# 05-USB-Prog.net
KiCad netlist of a schematic drawn in Altium Designer
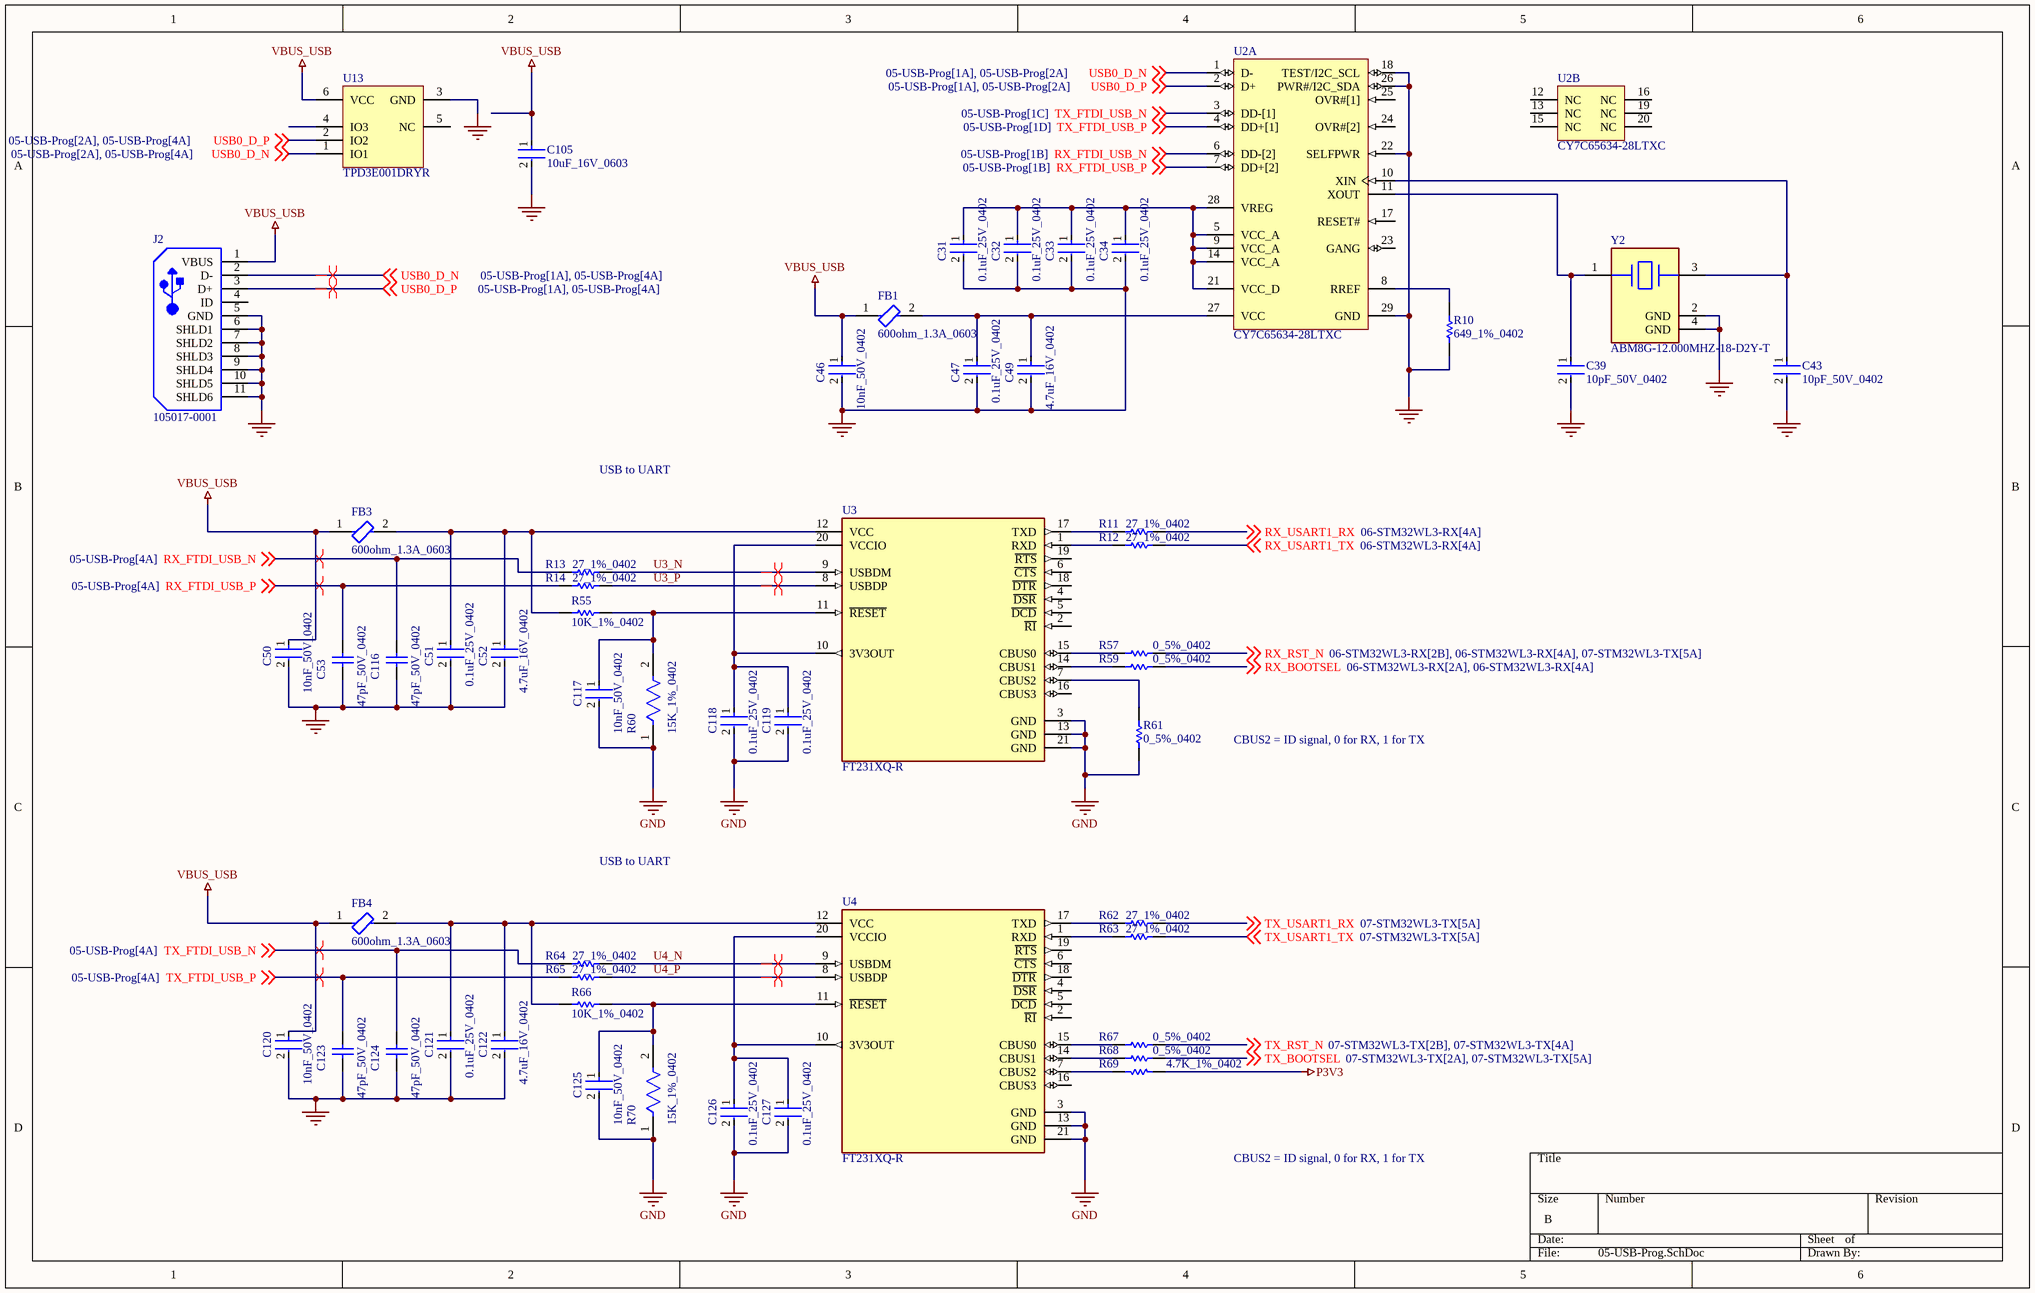
[diagram p0: 05-USB-Prog.SchDoc]

(export (version "E")
  (design (tool "Eeschema 10.0.6"))
  (components
    (comp (ref "C31")
      (value "0.1uF_25V_0402")
      (footprint "FP-0402-L_1_0_1-W_0_5_0_1-IPC_C")
      (description "General Purpose Ceramic Capacitor, 0402, 100nF, 10%, X7R, 15%, 25V")
      (fields (field (name "VOLTAGE") "25V") (field (name "TOLERANCE") "10%"))
      (libsource (lib "Altium Content Vault") (part "b4654b650e69147ec39a6b967a45e02"))
    )
    (comp (ref "C32")
      (value "0.1uF_25V_0402")
      (footprint "FP-0402-L_1_0_1-W_0_5_0_1-IPC_C")
      (description "General Purpose Ceramic Capacitor, 0402, 100nF, 10%, X7R, 15%, 25V")
      (fields (field (name "VOLTAGE") "25V") (field (name "TOLERANCE") "10%"))
      (libsource (lib "Altium Content Vault") (part "b4654b650e69147ec39a6b967a45e02"))
    )
    (comp (ref "C33")
      (value "0.1uF_25V_0402")
      (footprint "FP-0402-L_1_0_1-W_0_5_0_1-IPC_C")
      (description "General Purpose Ceramic Capacitor, 0402, 100nF, 10%, X7R, 15%, 25V")
      (fields (field (name "VOLTAGE") "25V") (field (name "TOLERANCE") "10%"))
      (libsource (lib "Altium Content Vault") (part "b4654b650e69147ec39a6b967a45e02"))
    )
    (comp (ref "C34")
      (value "0.1uF_25V_0402")
      (footprint "FP-0402-L_1_0_1-W_0_5_0_1-IPC_C")
      (description "General Purpose Ceramic Capacitor, 0402, 100nF, 10%, X7R, 15%, 25V")
      (fields (field (name "VOLTAGE") "25V") (field (name "TOLERANCE") "10%"))
      (libsource (lib "Altium Content Vault") (part "b4654b650e69147ec39a6b967a45e02"))
    )
    (comp (ref "C39")
      (value "10pF_50V_0402")
      (footprint "FP-C1005-050-0_05-IPC_C")
      (description "CAP CER 10PF 50V C0G 0402")
      (fields (field (name "VOLTAGE") "50V"))
      (libsource (lib "Altium Content Vault") (part "b4654b650e69147ec39a6b967a45e02"))
    )
    (comp (ref "C43")
      (value "10pF_50V_0402")
      (footprint "FP-C1005-050-0_05-IPC_C")
      (description "CAP CER 10PF 50V C0G 0402")
      (fields (field (name "VOLTAGE") "50V"))
      (libsource (lib "Altium Content Vault") (part "b4654b650e69147ec39a6b967a45e02"))
    )
    (comp (ref "C46")
      (value "10nF_50V_0402")
      (footprint "FP-CC0402-MFG")
      (description "CAP CER 10000PF 50V X7R 0402")
      (fields
        (field (name "OCTOPART") "https://octopart.com/cc0402krx7r9bb103-yageo-8376513")
        (field (name "MANUFACTURER PART NUMBER") "CC0402KRX7R9BB103")
      )
      (libsource (lib "Altium Content Vault") (part "11868f565c42a9108669ba33697ecf6"))
    )
    (comp (ref "C47")
      (value "0.1uF_25V_0402")
      (footprint "FP-0402-L_1_0_1-W_0_5_0_1-IPC_C")
      (description "General Purpose Ceramic Capacitor, 0402, 100nF, 10%, X7R, 15%, 25V")
      (fields (field (name "VOLTAGE") "25V") (field (name "TOLERANCE") "10%"))
      (libsource (lib "Altium Content Vault") (part "b4654b650e69147ec39a6b967a45e02"))
    )
    (comp (ref "C49")
      (value "4.7uF_16V_0402")
      (footprint "FP-CL829-IPC_C")
      (description "Cap Ceramic 4.7uF 16V X5R ±20% SMD 0402 +85°C Paper T/R")
      (fields (field (name "TOLERANCE") "20%"))
      (libsource (lib "Altium Content Vault") (part "b4654b650e69147ec39a6b967a45e02"))
    )
    (comp (ref "C50")
      (value "10nF_50V_0402")
      (footprint "FP-CC0402-MFG")
      (description "CAP CER 10000PF 50V X7R 0402")
      (fields
        (field (name "OCTOPART") "https://octopart.com/cc0402krx7r9bb103-yageo-8376513")
        (field (name "MANUFACTURER PART NUMBER") "CC0402KRX7R9BB103")
      )
      (libsource (lib "Altium Content Vault") (part "11868f565c42a9108669ba33697ecf6"))
    )
    (comp (ref "C51")
      (value "0.1uF_25V_0402")
      (footprint "FP-0402-L_1_0_1-W_0_5_0_1-IPC_C")
      (description "General Purpose Ceramic Capacitor, 0402, 100nF, 10%, X7R, 15%, 25V")
      (fields (field (name "VOLTAGE") "25V") (field (name "TOLERANCE") "10%"))
      (libsource (lib "Altium Content Vault") (part "b4654b650e69147ec39a6b967a45e02"))
    )
    (comp (ref "C52")
      (value "4.7uF_16V_0402")
      (footprint "FP-CL829-IPC_C")
      (description "Cap Ceramic 4.7uF 16V X5R ±20% SMD 0402 +85°C Paper T/R")
      (fields (field (name "TOLERANCE") "20%"))
      (libsource (lib "Altium Content Vault") (part "b4654b650e69147ec39a6b967a45e02"))
    )
    (comp (ref "C53")
      (value "47pF_50V_0402")
      (footprint "CAPC1005X55X25LL05T10")
      (fields (field (name "PART NUMBER") "GRM1555C1H470JA01D") (field (name "MANUFACTURER") "Murata"))
      (libsource (lib "Altium Content Vault") (part "CAP"))
    )
    (comp (ref "C105")
      (value "10uF_16V_0603")
      (footprint "FP-0603-L_1_6_0_2-W_0_8_0-MFG")
      (description "Multilayer Ceramic Capacitor 10uF 16V X5R 20% SMD 0603 T/R")
      (fields (field (name "TOLERANCE") "20%"))
      (libsource (lib "Altium Content Vault") (part "b4654b650e69147ec39a6b967a45e02"))
    )
    (comp (ref "C116")
      (value "47pF_50V_0402")
      (footprint "CAPC1005X55X25LL05T10")
      (fields (field (name "PART NUMBER") "GRM1555C1H470JA01D") (field (name "MANUFACTURER") "Murata"))
      (libsource (lib "Altium Content Vault") (part "CAP"))
    )
    (comp (ref "C117")
      (value "10nF_50V_0402")
      (footprint "FP-CC0402-MFG")
      (description "CAP CER 10000PF 50V X7R 0402")
      (fields
        (field (name "OCTOPART") "https://octopart.com/cc0402krx7r9bb103-yageo-8376513")
        (field (name "MANUFACTURER PART NUMBER") "CC0402KRX7R9BB103")
      )
      (libsource (lib "Altium Content Vault") (part "11868f565c42a9108669ba33697ecf6"))
    )
    (comp (ref "C118")
      (value "0.1uF_25V_0402")
      (footprint "FP-0402-L_1_0_1-W_0_5_0_1-IPC_C")
      (description "General Purpose Ceramic Capacitor, 0402, 100nF, 10%, X7R, 15%, 25V")
      (fields (field (name "VOLTAGE") "25V") (field (name "TOLERANCE") "10%"))
      (libsource (lib "Altium Content Vault") (part "b4654b650e69147ec39a6b967a45e02"))
    )
    (comp (ref "C119")
      (value "0.1uF_25V_0402")
      (footprint "FP-0402-L_1_0_1-W_0_5_0_1-IPC_C")
      (description "General Purpose Ceramic Capacitor, 0402, 100nF, 10%, X7R, 15%, 25V")
      (fields (field (name "VOLTAGE") "25V") (field (name "TOLERANCE") "10%"))
      (libsource (lib "Altium Content Vault") (part "b4654b650e69147ec39a6b967a45e02"))
    )
    (comp (ref "C120")
      (value "10nF_50V_0402")
      (footprint "FP-CC0402-MFG")
      (description "CAP CER 10000PF 50V X7R 0402")
      (fields
        (field (name "OCTOPART") "https://octopart.com/cc0402krx7r9bb103-yageo-8376513")
        (field (name "MANUFACTURER PART NUMBER") "CC0402KRX7R9BB103")
      )
      (libsource (lib "Altium Content Vault") (part "11868f565c42a9108669ba33697ecf6"))
    )
    (comp (ref "C121")
      (value "0.1uF_25V_0402")
      (footprint "FP-0402-L_1_0_1-W_0_5_0_1-IPC_C")
      (description "General Purpose Ceramic Capacitor, 0402, 100nF, 10%, X7R, 15%, 25V")
      (fields (field (name "VOLTAGE") "25V") (field (name "TOLERANCE") "10%"))
      (libsource (lib "Altium Content Vault") (part "b4654b650e69147ec39a6b967a45e02"))
    )
    (comp (ref "C122")
      (value "4.7uF_16V_0402")
      (footprint "FP-CL829-IPC_C")
      (description "Cap Ceramic 4.7uF 16V X5R ±20% SMD 0402 +85°C Paper T/R")
      (fields (field (name "TOLERANCE") "20%"))
      (libsource (lib "Altium Content Vault") (part "b4654b650e69147ec39a6b967a45e02"))
    )
    (comp (ref "C123")
      (value "47pF_50V_0402")
      (footprint "CAPC1005X55X25LL05T10")
      (fields (field (name "PART NUMBER") "GRM1555C1H470JA01D") (field (name "MANUFACTURER") "Murata"))
      (libsource (lib "Altium Content Vault") (part "CAP"))
    )
    (comp (ref "C124")
      (value "47pF_50V_0402")
      (footprint "CAPC1005X55X25LL05T10")
      (fields (field (name "PART NUMBER") "GRM1555C1H470JA01D") (field (name "MANUFACTURER") "Murata"))
      (libsource (lib "Altium Content Vault") (part "CAP"))
    )
    (comp (ref "C125")
      (value "10nF_50V_0402")
      (footprint "FP-CC0402-MFG")
      (description "CAP CER 10000PF 50V X7R 0402")
      (fields
        (field (name "OCTOPART") "https://octopart.com/cc0402krx7r9bb103-yageo-8376513")
        (field (name "MANUFACTURER PART NUMBER") "CC0402KRX7R9BB103")
      )
      (libsource (lib "Altium Content Vault") (part "11868f565c42a9108669ba33697ecf6"))
    )
    (comp (ref "C126")
      (value "0.1uF_25V_0402")
      (footprint "FP-0402-L_1_0_1-W_0_5_0_1-IPC_C")
      (description "General Purpose Ceramic Capacitor, 0402, 100nF, 10%, X7R, 15%, 25V")
      (fields (field (name "VOLTAGE") "25V") (field (name "TOLERANCE") "10%"))
      (libsource (lib "Altium Content Vault") (part "b4654b650e69147ec39a6b967a45e02"))
    )
    (comp (ref "C127")
      (value "0.1uF_25V_0402")
      (footprint "FP-0402-L_1_0_1-W_0_5_0_1-IPC_C")
      (description "General Purpose Ceramic Capacitor, 0402, 100nF, 10%, X7R, 15%, 25V")
      (fields (field (name "VOLTAGE") "25V") (field (name "TOLERANCE") "10%"))
      (libsource (lib "Altium Content Vault") (part "b4654b650e69147ec39a6b967a45e02"))
    )
    (comp (ref "FB1")
      (value "600ohm_1.3A_0603")
      (footprint "FP-BLM18-0_15-t0_8-IPC_A")
      (description "Chip Ferrite Bead, 0603, 600Ω @ 100MHz, 0.15Ω, 25%, 1.3A")
      (fields (field (name "TOLERANCE") "25%"))
      (libsource (lib "Altium Content Vault") (part "5f30dd21d616792df468990f7003faa"))
    )
    (comp (ref "FB3")
      (value "600ohm_1.3A_0603")
      (footprint "FP-BLM18-0_15-t0_8-IPC_A")
      (description "Chip Ferrite Bead, 0603, 600Ω @ 100MHz, 0.15Ω, 25%, 1.3A")
      (fields (field (name "TOLERANCE") "25%"))
      (libsource (lib "Altium Content Vault") (part "5f30dd21d616792df468990f7003faa"))
    )
    (comp (ref "FB4")
      (value "600ohm_1.3A_0603")
      (footprint "FP-BLM18-0_15-t0_8-IPC_A")
      (description "Chip Ferrite Bead, 0603, 600Ω @ 100MHz, 0.15Ω, 25%, 1.3A")
      (fields (field (name "TOLERANCE") "25%"))
      (libsource (lib "Altium Content Vault") (part "5f30dd21d616792df468990f7003faa"))
    )
    (comp (ref "J2")
      (value "105017-0001")
      (footprint "USB-MICRO-B_V")
      (fields (field (name "MANUFACTURER") "Molex"))
      (libsource (lib "Altium Content Vault") (part "USB-5-6SHLD"))
    )
    (comp (ref "R10")
      (value "649_1%_0402")
      (footprint "RESC1005X40X25LL05T05")
      (fields (field (name "PART NUMBER") "ERJ-2RKF6490X") (field (name "MANUFACTURER") "Panasonic"))
      (libsource (lib "Altium Content Vault") (part "RES"))
    )
    (comp (ref "R11")
      (value "27_1%_0402")
      (footprint "RESC1005X40X25NL05T05")
      (fields (field (name "PART NUMBER") "CRCW040227R0FKED") (field (name "MANUFACTURER") "Vishay Dale"))
      (libsource (lib "Altium Content Vault") (part "RES"))
    )
    (comp (ref "R12")
      (value "27_1%_0402")
      (footprint "RESC1005X40X25NL05T05")
      (fields (field (name "PART NUMBER") "CRCW040227R0FKED") (field (name "MANUFACTURER") "Vishay Dale"))
      (libsource (lib "Altium Content Vault") (part "RES"))
    )
    (comp (ref "R13")
      (value "27_1%_0402")
      (footprint "RESC1005X40X25NL05T05")
      (fields (field (name "PART NUMBER") "CRCW040227R0FKED") (field (name "MANUFACTURER") "Vishay Dale"))
      (libsource (lib "Altium Content Vault") (part "RES"))
    )
    (comp (ref "R14")
      (value "27_1%_0402")
      (footprint "RESC1005X40X25NL05T05")
      (fields (field (name "PART NUMBER") "CRCW040227R0FKED") (field (name "MANUFACTURER") "Vishay Dale"))
      (libsource (lib "Altium Content Vault") (part "RES"))
    )
    (comp (ref "R55")
      (value "10K_1%_0402")
      (footprint "RESC1005X40X25LL05T10")
      (fields (field (name "PART NUMBER") "RC0402FR-0710KL") (field (name "MANUFACTURER") "Yageo / Phycomp"))
      (libsource (lib "Altium Content Vault") (part "RES"))
    )
    (comp (ref "R57")
      (value "0_5%_0402")
      (footprint "RESC1005X40X25NL05T10")
      (fields (field (name "MANUFACTURER") "Panasonic") (field (name "PART NUMBER") "ERJ-U020R00X"))
      (libsource (lib "Altium Content Vault") (part "RES"))
    )
    (comp (ref "R59")
      (value "0_5%_0402")
      (footprint "RESC1005X40X25NL05T10")
      (fields (field (name "MANUFACTURER") "Panasonic") (field (name "PART NUMBER") "ERJ-U020R00X"))
      (libsource (lib "Altium Content Vault") (part "RES"))
    )
    (comp (ref "R60")
      (value "15K_1%_0402")
      (footprint "FP-ERJ2R-MFG")
      (description "RES SMD 15K OHM 1% 1/10W 0402")
      (fields (field (name "TOLERANCE") "1%") (field (name "MANUFACTURER PART NUMBER") "ERJ-2RKF1502X"))
      (libsource (lib "Altium Content Vault") (part "1029c3af85768c4190bb7ad29bc67b5"))
    )
    (comp (ref "R61")
      (value "0_5%_0402")
      (footprint "RESC1005X40X25NL05T10")
      (fields (field (name "MANUFACTURER") "Panasonic") (field (name "PART NUMBER") "ERJ-U020R00X"))
      (libsource (lib "Altium Content Vault") (part "RES"))
    )
    (comp (ref "R62")
      (value "27_1%_0402")
      (footprint "RESC1005X40X25NL05T05")
      (fields (field (name "PART NUMBER") "CRCW040227R0FKED") (field (name "MANUFACTURER") "Vishay Dale"))
      (libsource (lib "Altium Content Vault") (part "RES"))
    )
    (comp (ref "R63")
      (value "27_1%_0402")
      (footprint "RESC1005X40X25NL05T05")
      (fields (field (name "PART NUMBER") "CRCW040227R0FKED") (field (name "MANUFACTURER") "Vishay Dale"))
      (libsource (lib "Altium Content Vault") (part "RES"))
    )
    (comp (ref "R64")
      (value "27_1%_0402")
      (footprint "RESC1005X40X25NL05T05")
      (fields (field (name "PART NUMBER") "CRCW040227R0FKED") (field (name "MANUFACTURER") "Vishay Dale"))
      (libsource (lib "Altium Content Vault") (part "RES"))
    )
    (comp (ref "R65")
      (value "27_1%_0402")
      (footprint "RESC1005X40X25NL05T05")
      (fields (field (name "PART NUMBER") "CRCW040227R0FKED") (field (name "MANUFACTURER") "Vishay Dale"))
      (libsource (lib "Altium Content Vault") (part "RES"))
    )
    (comp (ref "R66")
      (value "10K_1%_0402")
      (footprint "RESC1005X40X25LL05T10")
      (fields (field (name "PART NUMBER") "RC0402FR-0710KL") (field (name "MANUFACTURER") "Yageo / Phycomp"))
      (libsource (lib "Altium Content Vault") (part "RES"))
    )
    (comp (ref "R67")
      (value "0_5%_0402")
      (footprint "RESC1005X40X25NL05T10")
      (fields (field (name "MANUFACTURER") "Panasonic") (field (name "PART NUMBER") "ERJ-U020R00X"))
      (libsource (lib "Altium Content Vault") (part "RES"))
    )
    (comp (ref "R68")
      (value "0_5%_0402")
      (footprint "RESC1005X40X25NL05T10")
      (fields (field (name "MANUFACTURER") "Panasonic") (field (name "PART NUMBER") "ERJ-U020R00X"))
      (libsource (lib "Altium Content Vault") (part "RES"))
    )
    (comp (ref "R69")
      (value "4.7K_1%_0402")
      (footprint "RESC1005X40X25NL10T10")
      (fields (field (name "MANUFACTURER") "Bourns") (field (name "PART NUMBER") "CR0402-FX-4701GLF"))
      (libsource (lib "Altium Content Vault") (part "RES"))
    )
    (comp (ref "R70")
      (value "15K_1%_0402")
      (footprint "FP-ERJ2R-MFG")
      (description "RES SMD 15K OHM 1% 1/10W 0402")
      (fields (field (name "TOLERANCE") "1%") (field (name "MANUFACTURER PART NUMBER") "ERJ-2RKF1502X"))
      (libsource (lib "Altium Content Vault") (part "1029c3af85768c4190bb7ad29bc67b5"))
    )
    (comp (ref "U2")
      (value "CY7C65634-28LTXC")
      (footprint "CYP-LTX28_M")
      (fields (field (name "MANUFACTURER") "Cypress"))
      (libsource (lib "Altium Content Vault") (part "CYP-CY7C65634-LT28"))
    )
    (comp (ref "U3")
      (value "FT231XQ-R")
      (footprint "FP-QFN-20-MFG")
      (description "IC USB SERIAL FULL UART 20QFN")
      (libsource (lib "Altium Content Vault") (part "1a58eaec777a01ae16a7011961d8d4e"))
    )
    (comp (ref "U4")
      (value "FT231XQ-R")
      (footprint "FP-QFN-20-MFG")
      (description "IC USB SERIAL FULL UART 20QFN")
      (libsource (lib "Altium Content Vault") (part "1a58eaec777a01ae16a7011961d8d4e"))
    )
    (comp (ref "U13")
      (value "TPD3E001DRYR")
      (footprint "DRY0006A")
      (fields (field (name "MANUFACTURER") "Texas Instruments"))
      (libsource (lib "Altium Content Vault") (part "TI-TPD3E001-SON_DRY-6"))
    )
    (comp (ref "Y2")
      (value "ABM8G-12.000MHZ-18-D2Y-T")
      (footprint "FP-ABM8G-MFG")
      (description "Crystal 12MHz ±20ppm (Tol) ±30ppm (Stability) 18pF FUND 120Ω 4-Pin SMD T/R")
      (fields (field (name "TOLERANCE") "20ppm"))
      (libsource (lib "Altium Content Vault") (part "48e526d86b7f2615d98721063c72f49"))
    )
  )
  (nets
    (net (code "1") (name "/U3_N") (class "Default")
      (node (ref "R13") (pin "2") (pinfunction "2_2") (pintype "passive"))
      (node (ref "U3") (pin "9") (pinfunction "USBDM_9") (pintype "input"))
    )
    (net (code "2") (name "/U3_P") (class "Default")
      (node (ref "R14") (pin "2") (pinfunction "2_2") (pintype "passive"))
      (node (ref "U3") (pin "8") (pinfunction "USBDP_8") (pintype "input"))
    )
    (net (code "3") (name "/U4_N") (class "Default")
      (node (ref "R64") (pin "2") (pinfunction "2_2") (pintype "passive"))
      (node (ref "U4") (pin "9") (pinfunction "USBDM_9") (pintype "input"))
    )
    (net (code "4") (name "/U4_P") (class "Default")
      (node (ref "R65") (pin "2") (pinfunction "2_2") (pintype "passive"))
      (node (ref "U4") (pin "8") (pinfunction "USBDP_8") (pintype "input"))
    )
    (net (code "5") (name "GND") (class "Default")
      (node (ref "C105") (pin "2") (pinfunction "2_2") (pintype "passive"))
      (node (ref "C116") (pin "1") (pinfunction "1_1") (pintype "passive"))
      (node (ref "C117") (pin "2") (pinfunction "2_2") (pintype "passive"))
      (node (ref "C118") (pin "2") (pinfunction "2_2") (pintype "passive"))
      (node (ref "C119") (pin "2") (pinfunction "2_2") (pintype "passive"))
      (node (ref "C120") (pin "2") (pinfunction "2_2") (pintype "passive"))
      (node (ref "C121") (pin "2") (pinfunction "2_2") (pintype "passive"))
      (node (ref "C122") (pin "2") (pinfunction "2_2") (pintype "passive"))
      (node (ref "C123") (pin "1") (pinfunction "1_1") (pintype "passive"))
      (node (ref "C124") (pin "1") (pinfunction "1_1") (pintype "passive"))
      (node (ref "C125") (pin "2") (pinfunction "2_2") (pintype "passive"))
      (node (ref "C126") (pin "2") (pinfunction "2_2") (pintype "passive"))
      (node (ref "C127") (pin "2") (pinfunction "2_2") (pintype "passive"))
      (node (ref "C31") (pin "2") (pinfunction "2_2") (pintype "passive"))
      (node (ref "C32") (pin "2") (pinfunction "2_2") (pintype "passive"))
      (node (ref "C33") (pin "2") (pinfunction "2_2") (pintype "passive"))
      (node (ref "C34") (pin "2") (pinfunction "2_2") (pintype "passive"))
      (node (ref "C39") (pin "2") (pinfunction "2_2") (pintype "passive"))
      (node (ref "C43") (pin "2") (pinfunction "2_2") (pintype "passive"))
      (node (ref "C46") (pin "2") (pinfunction "2_2") (pintype "passive"))
      (node (ref "C47") (pin "2") (pinfunction "2_2") (pintype "passive"))
      (node (ref "C49") (pin "2") (pinfunction "2_2") (pintype "passive"))
      (node (ref "C50") (pin "2") (pinfunction "2_2") (pintype "passive"))
      (node (ref "C51") (pin "2") (pinfunction "2_2") (pintype "passive"))
      (node (ref "C52") (pin "2") (pinfunction "2_2") (pintype "passive"))
      (node (ref "C53") (pin "1") (pinfunction "1_1") (pintype "passive"))
      (node (ref "J2") (pin "10") (pinfunction "SHLD5_10") (pintype "passive"))
      (node (ref "J2") (pin "11") (pinfunction "SHLD6_11") (pintype "passive"))
      (node (ref "J2") (pin "5") (pinfunction "GND_5") (pintype "passive"))
      (node (ref "J2") (pin "6") (pinfunction "SHLD1_6") (pintype "passive"))
      (node (ref "J2") (pin "7") (pinfunction "SHLD2_7") (pintype "passive"))
      (node (ref "J2") (pin "8") (pinfunction "SHLD3_8") (pintype "passive"))
      (node (ref "J2") (pin "9") (pinfunction "SHLD4_9") (pintype "passive"))
      (node (ref "R10") (pin "1") (pinfunction "1_1") (pintype "passive"))
      (node (ref "R60") (pin "1") (pinfunction "1_1") (pintype "passive"))
      (node (ref "R61") (pin "1") (pinfunction "1_1") (pintype "passive"))
      (node (ref "R70") (pin "1") (pinfunction "1_1") (pintype "passive"))
      (node (ref "U13") (pin "3") (pinfunction "GND_3") (pintype "power_in"))
      (node (ref "U2") (pin "18") (pinfunction "TEST/I2C_SCL_18") (pintype "bidirectional"))
      (node (ref "U2") (pin "22") (pinfunction "SELFPWR_22") (pintype "input"))
      (node (ref "U2") (pin "26") (pinfunction "PWR#/I2C_SDA_26") (pintype "bidirectional"))
      (node (ref "U2") (pin "29") (pinfunction "GND_29") (pintype "power_in"))
      (node (ref "U3") (pin "13") (pinfunction "GND_13") (pintype "open_emitter"))
      (node (ref "U3") (pin "21") (pinfunction "GND_21") (pintype "power_in"))
      (node (ref "U3") (pin "3") (pinfunction "GND_3") (pintype "power_in"))
      (node (ref "U4") (pin "13") (pinfunction "GND_13") (pintype "open_emitter"))
      (node (ref "U4") (pin "21") (pinfunction "GND_21") (pintype "power_in"))
      (node (ref "U4") (pin "3") (pinfunction "GND_3") (pintype "power_in"))
      (node (ref "Y2") (pin "2") (pinfunction "GND_2") (pintype "power_in"))
      (node (ref "Y2") (pin "4") (pinfunction "GND_4") (pintype "power_in"))
    )
    (net (code "6") (name "Net-(U2A-RREF)") (class "Default")
      (node (ref "R10") (pin "2") (pinfunction "2_2") (pintype "passive"))
      (node (ref "U2") (pin "8") (pinfunction "RREF_8") (pintype "passive"))
    )
    (net (code "7") (name "Net-(U2A-VCC)") (class "Default")
      (node (ref "C47") (pin "1") (pinfunction "1_1") (pintype "passive"))
      (node (ref "C49") (pin "1") (pinfunction "1_1") (pintype "passive"))
      (node (ref "FB1") (pin "2") (pinfunction "2_2") (pintype "passive"))
      (node (ref "U2") (pin "27") (pinfunction "VCC_27") (pintype "power_in"))
    )
    (net (code "8") (name "Net-(U2A-VCC_D)") (class "Default")
      (node (ref "C31") (pin "1") (pinfunction "1_1") (pintype "passive"))
      (node (ref "C32") (pin "1") (pinfunction "1_1") (pintype "passive"))
      (node (ref "C33") (pin "1") (pinfunction "1_1") (pintype "passive"))
      (node (ref "C34") (pin "1") (pinfunction "1_1") (pintype "passive"))
      (node (ref "U2") (pin "14") (pinfunction "VCC_A_14") (pintype "power_in"))
      (node (ref "U2") (pin "21") (pinfunction "VCC_D_21") (pintype "power_in"))
      (node (ref "U2") (pin "28") (pinfunction "VREG_28") (pintype "power_in"))
      (node (ref "U2") (pin "5") (pinfunction "VCC_A_5") (pintype "power_in"))
      (node (ref "U2") (pin "9") (pinfunction "VCC_A_9") (pintype "power_in"))
    )
    (net (code "9") (name "Net-(U2A-XIN)") (class "Default")
      (node (ref "C43") (pin "1") (pinfunction "1_1") (pintype "passive"))
      (node (ref "U2") (pin "10") (pinfunction "XIN_10") (pintype "input"))
      (node (ref "Y2") (pin "3") (pinfunction "3_3") (pintype "passive"))
    )
    (net (code "10") (name "Net-(U2A-XOUT)") (class "Default")
      (node (ref "C39") (pin "1") (pinfunction "1_1") (pintype "passive"))
      (node (ref "U2") (pin "11") (pinfunction "XOUT_11") (pintype "passive"))
      (node (ref "Y2") (pin "1") (pinfunction "1_1") (pintype "passive"))
    )
    (net (code "11") (name "Net-(U3-3V3OUT)") (class "Default")
      (node (ref "C118") (pin "1") (pinfunction "1_1") (pintype "passive"))
      (node (ref "C119") (pin "1") (pinfunction "1_1") (pintype "passive"))
      (node (ref "U3") (pin "10") (pinfunction "3V3OUT_10") (pintype "output"))
      (node (ref "U3") (pin "20") (pinfunction "VCCIO_20") (pintype "power_in"))
    )
    (net (code "12") (name "Net-(U3-CBUS0)") (class "Default")
      (node (ref "R57") (pin "1") (pinfunction "1_1") (pintype "passive"))
      (node (ref "U3") (pin "15") (pinfunction "CBUS0_15") (pintype "bidirectional"))
    )
    (net (code "13") (name "Net-(U3-CBUS1)") (class "Default")
      (node (ref "R59") (pin "1") (pinfunction "1_1") (pintype "passive"))
      (node (ref "U3") (pin "14") (pinfunction "CBUS1_14") (pintype "bidirectional"))
    )
    (net (code "14") (name "Net-(U3-CBUS2)") (class "Default")
      (node (ref "R61") (pin "2") (pinfunction "2_2") (pintype "passive"))
      (node (ref "U3") (pin "7") (pinfunction "CBUS2_7") (pintype "bidirectional"))
    )
    (net (code "15") (name "Net-(U3-RXD)") (class "Default")
      (node (ref "R12") (pin "1") (pinfunction "1_1") (pintype "passive"))
      (node (ref "U3") (pin "1") (pinfunction "RXD_1") (pintype "input"))
    )
    (net (code "16") (name "Net-(U3-TXD)") (class "Default")
      (node (ref "R11") (pin "1") (pinfunction "1_1") (pintype "passive"))
      (node (ref "U3") (pin "17") (pinfunction "TXD_17") (pintype "output"))
    )
    (net (code "17") (name "Net-(U3-VCC)") (class "Default")
      (node (ref "C51") (pin "1") (pinfunction "1_1") (pintype "passive"))
      (node (ref "C52") (pin "1") (pinfunction "1_1") (pintype "passive"))
      (node (ref "FB3") (pin "2") (pinfunction "2_2") (pintype "passive"))
      (node (ref "R55") (pin "2") (pinfunction "2_2") (pintype "passive"))
      (node (ref "U3") (pin "12") (pinfunction "VCC_12") (pintype "power_in"))
    )
    (net (code "18") (name "Net-(U3-~{RESET})") (class "Default")
      (node (ref "C117") (pin "1") (pinfunction "1_1") (pintype "passive"))
      (node (ref "R55") (pin "1") (pinfunction "1_1") (pintype "passive"))
      (node (ref "R60") (pin "2") (pinfunction "2_2") (pintype "passive"))
      (node (ref "U3") (pin "11") (pinfunction "~{RESET}_11") (pintype "input"))
    )
    (net (code "19") (name "Net-(U4-3V3OUT)") (class "Default")
      (node (ref "C126") (pin "1") (pinfunction "1_1") (pintype "passive"))
      (node (ref "C127") (pin "1") (pinfunction "1_1") (pintype "passive"))
      (node (ref "U4") (pin "10") (pinfunction "3V3OUT_10") (pintype "output"))
      (node (ref "U4") (pin "20") (pinfunction "VCCIO_20") (pintype "power_in"))
    )
    (net (code "20") (name "Net-(U4-CBUS0)") (class "Default")
      (node (ref "R67") (pin "1") (pinfunction "1_1") (pintype "passive"))
      (node (ref "U4") (pin "15") (pinfunction "CBUS0_15") (pintype "bidirectional"))
    )
    (net (code "21") (name "Net-(U4-CBUS1)") (class "Default")
      (node (ref "R68") (pin "1") (pinfunction "1_1") (pintype "passive"))
      (node (ref "U4") (pin "14") (pinfunction "CBUS1_14") (pintype "bidirectional"))
    )
    (net (code "22") (name "Net-(U4-CBUS2)") (class "Default")
      (node (ref "R69") (pin "2") (pinfunction "2_2") (pintype "passive"))
      (node (ref "U4") (pin "7") (pinfunction "CBUS2_7") (pintype "bidirectional"))
    )
    (net (code "23") (name "Net-(U4-RXD)") (class "Default")
      (node (ref "R63") (pin "1") (pinfunction "1_1") (pintype "passive"))
      (node (ref "U4") (pin "1") (pinfunction "RXD_1") (pintype "input"))
    )
    (net (code "24") (name "Net-(U4-TXD)") (class "Default")
      (node (ref "R62") (pin "1") (pinfunction "1_1") (pintype "passive"))
      (node (ref "U4") (pin "17") (pinfunction "TXD_17") (pintype "output"))
    )
    (net (code "25") (name "Net-(U4-VCC)") (class "Default")
      (node (ref "C121") (pin "1") (pinfunction "1_1") (pintype "passive"))
      (node (ref "C122") (pin "1") (pinfunction "1_1") (pintype "passive"))
      (node (ref "FB4") (pin "2") (pinfunction "2_2") (pintype "passive"))
      (node (ref "R66") (pin "2") (pinfunction "2_2") (pintype "passive"))
      (node (ref "U4") (pin "12") (pinfunction "VCC_12") (pintype "power_in"))
    )
    (net (code "26") (name "Net-(U4-~{RESET})") (class "Default")
      (node (ref "C125") (pin "1") (pinfunction "1_1") (pintype "passive"))
      (node (ref "R66") (pin "1") (pinfunction "1_1") (pintype "passive"))
      (node (ref "R70") (pin "2") (pinfunction "2_2") (pintype "passive"))
      (node (ref "U4") (pin "11") (pinfunction "~{RESET}_11") (pintype "input"))
    )
    (net (code "27") (name "P3V3") (class "Default")
      (node (ref "R69") (pin "1") (pinfunction "1_1") (pintype "passive"))
    )
    (net (code "28") (name "RX_BOOTSEL") (class "Default")
      (node (ref "R59") (pin "2") (pinfunction "2_2") (pintype "passive"))
    )
    (net (code "29") (name "RX_FTDI_USB_N") (class "Default")
      (node (ref "C116") (pin "2") (pinfunction "2_2") (pintype "passive"))
      (node (ref "R13") (pin "1") (pinfunction "1_1") (pintype "passive"))
      (node (ref "U2") (pin "6") (pinfunction "DD-[2]_6") (pintype "bidirectional"))
    )
    (net (code "30") (name "RX_FTDI_USB_P") (class "Default")
      (node (ref "C53") (pin "2") (pinfunction "2_2") (pintype "passive"))
      (node (ref "R14") (pin "1") (pinfunction "1_1") (pintype "passive"))
      (node (ref "U2") (pin "7") (pinfunction "DD+[2]_7") (pintype "bidirectional"))
    )
    (net (code "31") (name "RX_RST_N") (class "Default")
      (node (ref "R57") (pin "2") (pinfunction "2_2") (pintype "passive"))
    )
    (net (code "32") (name "RX_USART1_RX") (class "Default")
      (node (ref "R11") (pin "2") (pinfunction "2_2") (pintype "passive"))
    )
    (net (code "33") (name "RX_USART1_TX") (class "Default")
      (node (ref "R12") (pin "2") (pinfunction "2_2") (pintype "passive"))
    )
    (net (code "34") (name "TX_BOOTSEL") (class "Default")
      (node (ref "R68") (pin "2") (pinfunction "2_2") (pintype "passive"))
    )
    (net (code "35") (name "TX_FTDI_USB_N") (class "Default")
      (node (ref "C124") (pin "2") (pinfunction "2_2") (pintype "passive"))
      (node (ref "R64") (pin "1") (pinfunction "1_1") (pintype "passive"))
      (node (ref "U2") (pin "3") (pinfunction "DD-[1]_3") (pintype "bidirectional"))
    )
    (net (code "36") (name "TX_FTDI_USB_P") (class "Default")
      (node (ref "C123") (pin "2") (pinfunction "2_2") (pintype "passive"))
      (node (ref "R65") (pin "1") (pinfunction "1_1") (pintype "passive"))
      (node (ref "U2") (pin "4") (pinfunction "DD+[1]_4") (pintype "bidirectional"))
    )
    (net (code "37") (name "TX_RST_N") (class "Default")
      (node (ref "R67") (pin "2") (pinfunction "2_2") (pintype "passive"))
    )
    (net (code "38") (name "TX_USART1_RX") (class "Default")
      (node (ref "R62") (pin "2") (pinfunction "2_2") (pintype "passive"))
    )
    (net (code "39") (name "TX_USART1_TX") (class "Default")
      (node (ref "R63") (pin "2") (pinfunction "2_2") (pintype "passive"))
    )
    (net (code "40") (name "USB0_D_N") (class "Default")
      (node (ref "J2") (pin "2") (pinfunction "D-_2") (pintype "passive"))
      (node (ref "U13") (pin "1") (pinfunction "IO1_1") (pintype "passive"))
      (node (ref "U2") (pin "1") (pinfunction "D-_1") (pintype "bidirectional"))
    )
    (net (code "41") (name "USB0_D_P") (class "Default")
      (node (ref "J2") (pin "3") (pinfunction "D+_3") (pintype "passive"))
      (node (ref "U13") (pin "2") (pinfunction "IO2_2") (pintype "passive"))
      (node (ref "U2") (pin "2") (pinfunction "D+_2") (pintype "bidirectional"))
    )
    (net (code "42") (name "VBUS_USB") (class "Default")
      (node (ref "C105") (pin "1") (pinfunction "1_1") (pintype "passive"))
      (node (ref "C120") (pin "1") (pinfunction "1_1") (pintype "passive"))
      (node (ref "C46") (pin "1") (pinfunction "1_1") (pintype "passive"))
      (node (ref "C50") (pin "1") (pinfunction "1_1") (pintype "passive"))
      (node (ref "FB1") (pin "1") (pinfunction "1_1") (pintype "passive"))
      (node (ref "FB3") (pin "1") (pinfunction "1_1") (pintype "passive"))
      (node (ref "FB4") (pin "1") (pinfunction "1_1") (pintype "passive"))
      (node (ref "J2") (pin "1") (pinfunction "VBUS_1") (pintype "passive"))
      (node (ref "U13") (pin "6") (pinfunction "VCC_6") (pintype "power_in"))
    )
    (net (code "43") (name "unconnected-(J2-ID-Pad4)") (class "Default")
      (node (ref "J2") (pin "4") (pinfunction "ID_4") (pintype "passive"))
    )
    (net (code "44") (name "unconnected-(U2A-GANG-Pad23)") (class "Default")
      (node (ref "U2") (pin "23") (pinfunction "GANG_23") (pintype "bidirectional"))
    )
    (net (code "45") (name "unconnected-(U2A-OVR#[1]-Pad25)") (class "Default")
      (node (ref "U2") (pin "25") (pinfunction "OVR#[1]_25") (pintype "input"))
    )
    (net (code "46") (name "unconnected-(U2A-OVR#[2]-Pad24)") (class "Default")
      (node (ref "U2") (pin "24") (pinfunction "OVR#[2]_24") (pintype "input"))
    )
    (net (code "47") (name "unconnected-(U2A-RESET#-Pad17)") (class "Default")
      (node (ref "U2") (pin "17") (pinfunction "RESET#_17") (pintype "input"))
    )
    (net (code "48") (name "unconnected-(U2B-NC-Pad12)") (class "Default")
      (node (ref "U2") (pin "12") (pinfunction "NC_12") (pintype "passive"))
    )
    (net (code "49") (name "unconnected-(U2B-NC-Pad13)") (class "Default")
      (node (ref "U2") (pin "13") (pinfunction "NC_13") (pintype "passive"))
    )
    (net (code "50") (name "unconnected-(U2B-NC-Pad15)") (class "Default")
      (node (ref "U2") (pin "15") (pinfunction "NC_15") (pintype "passive"))
    )
    (net (code "51") (name "unconnected-(U2B-NC-Pad16)") (class "Default")
      (node (ref "U2") (pin "16") (pinfunction "NC_16") (pintype "passive"))
    )
    (net (code "52") (name "unconnected-(U2B-NC-Pad19)") (class "Default")
      (node (ref "U2") (pin "19") (pinfunction "NC_19") (pintype "passive"))
    )
    (net (code "53") (name "unconnected-(U2B-NC-Pad20)") (class "Default")
      (node (ref "U2") (pin "20") (pinfunction "NC_20") (pintype "passive"))
    )
    (net (code "54") (name "unconnected-(U3-CBUS3-Pad16)") (class "Default")
      (node (ref "U3") (pin "16") (pinfunction "CBUS3_16") (pintype "bidirectional"))
    )
    (net (code "55") (name "unconnected-(U3-~{CTS}-Pad6)") (class "Default")
      (node (ref "U3") (pin "6") (pinfunction "~{CTS}_6") (pintype "input"))
    )
    (net (code "56") (name "unconnected-(U3-~{DCD}-Pad5)") (class "Default")
      (node (ref "U3") (pin "5") (pinfunction "~{DCD}_5") (pintype "input"))
    )
    (net (code "57") (name "unconnected-(U3-~{DSR}-Pad4)") (class "Default")
      (node (ref "U3") (pin "4") (pinfunction "~{DSR}_4") (pintype "input"))
    )
    (net (code "58") (name "unconnected-(U3-~{DTR}-Pad18)") (class "Default")
      (node (ref "U3") (pin "18") (pinfunction "~{DTR}_18") (pintype "output"))
    )
    (net (code "59") (name "unconnected-(U3-~{RI}-Pad2)") (class "Default")
      (node (ref "U3") (pin "2") (pinfunction "~{RI}_2") (pintype "input"))
    )
    (net (code "60") (name "unconnected-(U3-~{RTS}-Pad19)") (class "Default")
      (node (ref "U3") (pin "19") (pinfunction "~{RTS}_19") (pintype "output"))
    )
    (net (code "61") (name "unconnected-(U4-CBUS3-Pad16)") (class "Default")
      (node (ref "U4") (pin "16") (pinfunction "CBUS3_16") (pintype "bidirectional"))
    )
    (net (code "62") (name "unconnected-(U4-~{CTS}-Pad6)") (class "Default")
      (node (ref "U4") (pin "6") (pinfunction "~{CTS}_6") (pintype "input"))
    )
    (net (code "63") (name "unconnected-(U4-~{DCD}-Pad5)") (class "Default")
      (node (ref "U4") (pin "5") (pinfunction "~{DCD}_5") (pintype "input"))
    )
    (net (code "64") (name "unconnected-(U4-~{DSR}-Pad4)") (class "Default")
      (node (ref "U4") (pin "4") (pinfunction "~{DSR}_4") (pintype "input"))
    )
    (net (code "65") (name "unconnected-(U4-~{DTR}-Pad18)") (class "Default")
      (node (ref "U4") (pin "18") (pinfunction "~{DTR}_18") (pintype "output"))
    )
    (net (code "66") (name "unconnected-(U4-~{RI}-Pad2)") (class "Default")
      (node (ref "U4") (pin "2") (pinfunction "~{RI}_2") (pintype "input"))
    )
    (net (code "67") (name "unconnected-(U4-~{RTS}-Pad19)") (class "Default")
      (node (ref "U4") (pin "19") (pinfunction "~{RTS}_19") (pintype "output"))
    )
    (net (code "68") (name "unconnected-(U13-IO3-Pad4)") (class "Default")
      (node (ref "U13") (pin "4") (pinfunction "IO3_4") (pintype "passive"))
    )
    (net (code "69") (name "unconnected-(U13-NC-Pad5)") (class "Default")
      (node (ref "U13") (pin "5") (pinfunction "NC_5") (pintype "passive"))
    )
  )
)
